# Connectors.net
KiCad netlist of a schematic drawn in Altium Designer
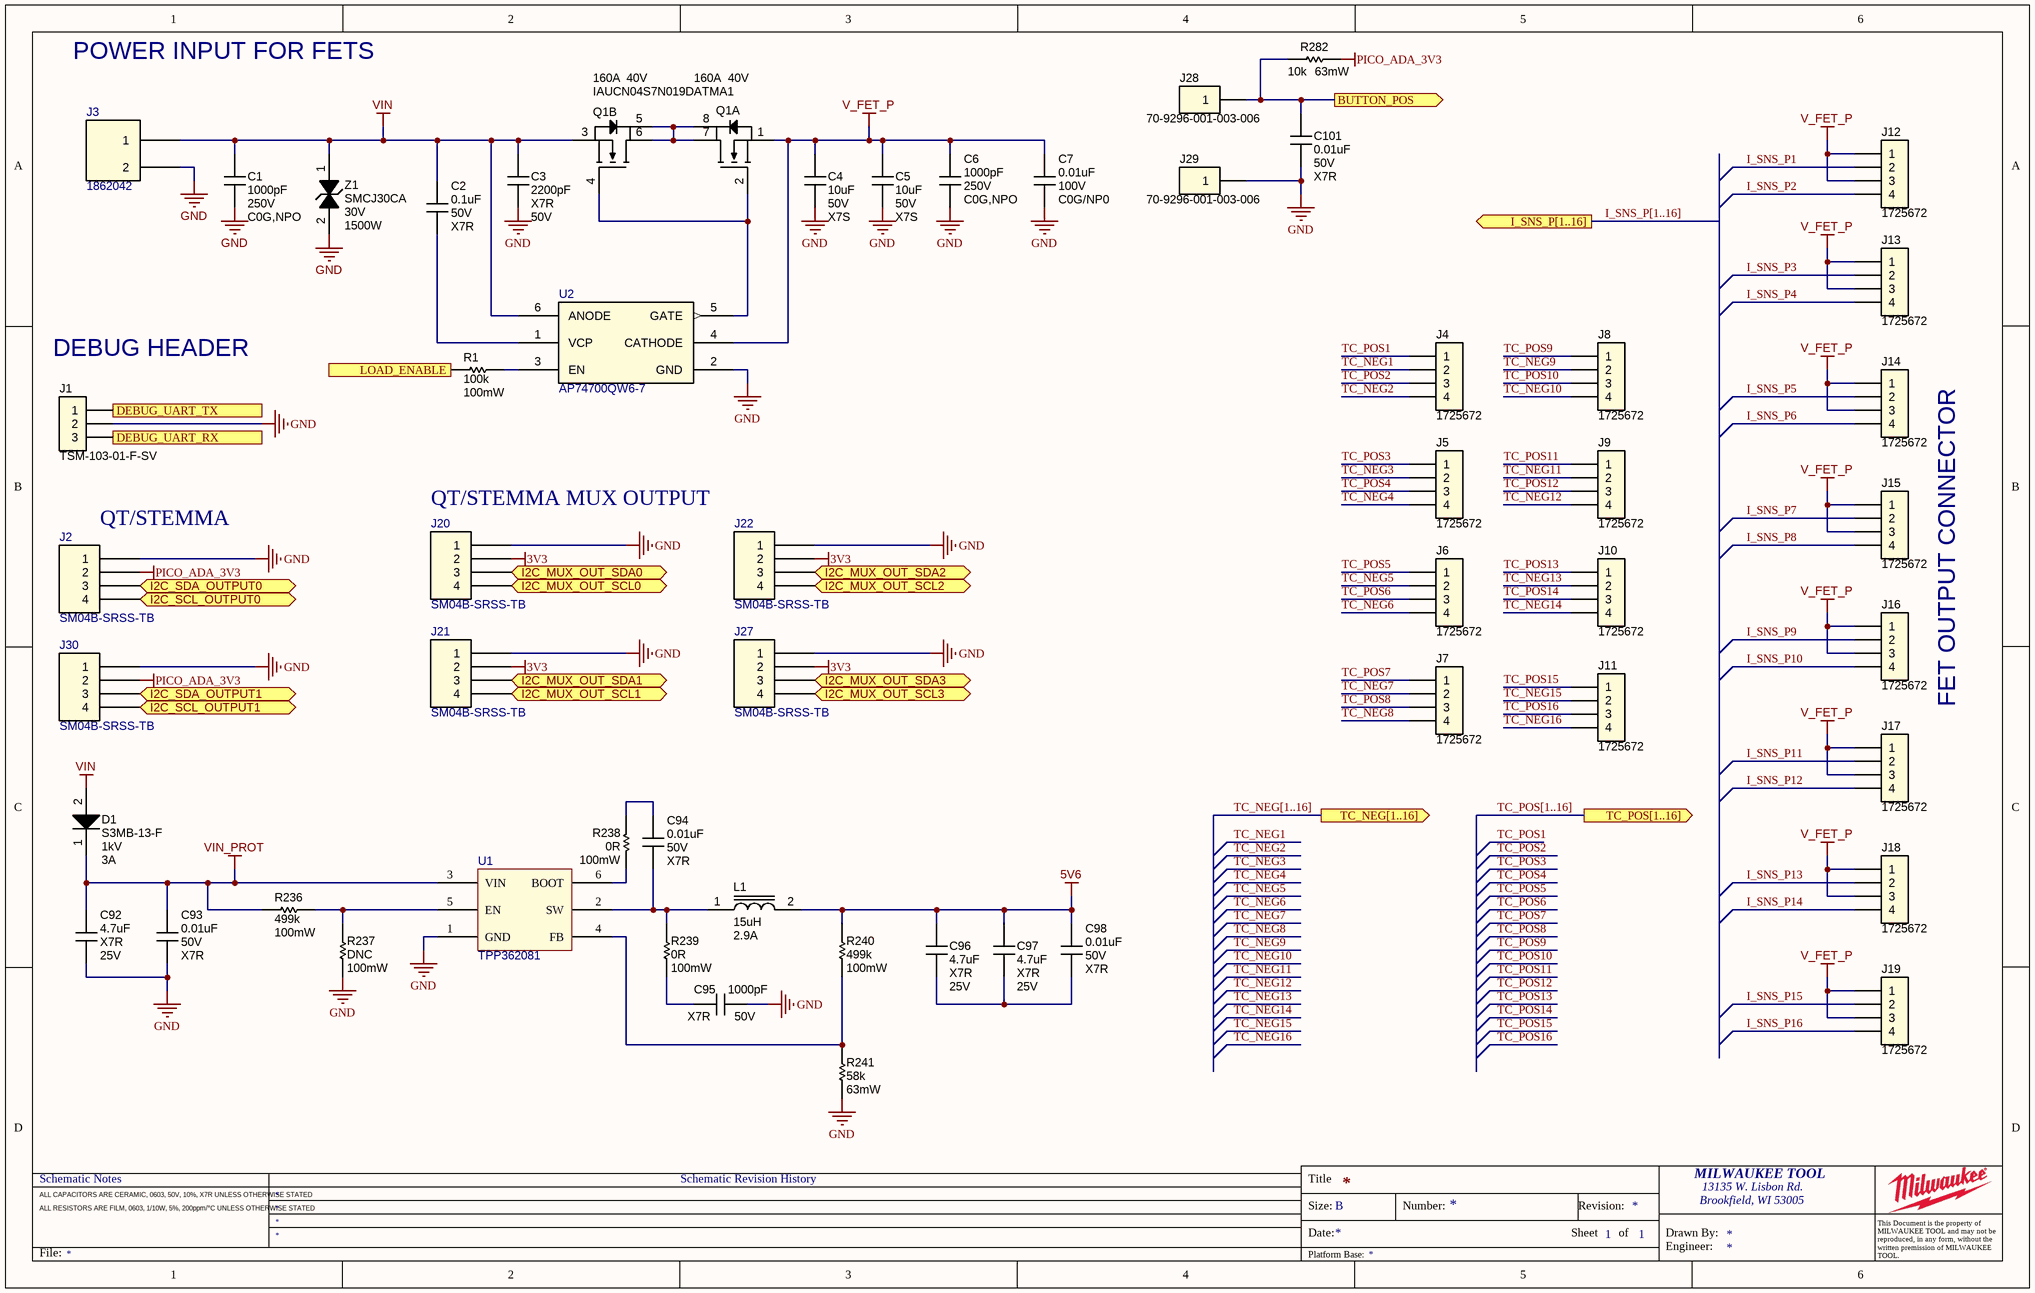
[diagram p0: Connectors.SchDoc]

(export (version "E")
  (design (tool "Eeschema 10.0.6"))
  (components
    (comp (ref "C1")
      (value "1000pF")
      (footprint "CAPC1608X09N")
      (description "CAP CER 1000PF 250V X7R 0603")
      (fields
        (field (name "TOLERANCE") "5%")
        (field (name "MFR") "KEMET")
        (field (name "VOLTAGE RATING") "250V")
        (field (name "TEMP COEFF") "C0G,NPO")
      )
      (libsource (lib "General_Library") (part "CMP-004-0013"))
    )
    (comp (ref "C2")
      (value "0.1uF")
      (footprint "CAPC1005X06N")
      (description "CAP CER SMD 0.1UF 50V X7R 0402")
      (fields
        (field (name "TOLERANCE") "10%")
        (field (name "MFR") "Murata Electronics")
        (field (name "VOLTAGE RATING") "50V")
        (field (name "TEMP COEFF") "X7R")
      )
      (libsource (lib "General_Library") (part "CMP-004-0076"))
    )
    (comp (ref "C3")
      (value "2200pF")
      (footprint "CAPC1608X09N")
      (description "CAP CER 2200PF 50V X7R 0603")
      (fields
        (field (name "TOLERANCE") "10%")
        (field (name "MFR") "KEMET")
        (field (name "TEMP COEFF") "X7R")
        (field (name "VOLTAGE RATING") "50V")
      )
      (libsource (lib "General_Library") (part "CMP-004-0009"))
    )
    (comp (ref "C4")
      (value "10uF")
      (footprint "CAPC3225X28N")
      (description "CAP, CER, 10µF, 50V, 10%, X7S, 1210")
      (fields
        (field (name "MFR") "TDK Corporation")
        (field (name "TOLERANCE") "10%")
        (field (name "VOLTAGE RATING") "50V")
        (field (name "TEMP COEFF") "X7S")
      )
      (libsource (lib "General_Library") (part "CMP-004-0001"))
    )
    (comp (ref "C5")
      (value "10uF")
      (footprint "CAPC3225X28N")
      (description "CAP, CER, 10µF, 50V, 10%, X7S, 1210")
      (fields
        (field (name "MFR") "TDK Corporation")
        (field (name "TOLERANCE") "10%")
        (field (name "VOLTAGE RATING") "50V")
        (field (name "TEMP COEFF") "X7S")
      )
      (libsource (lib "General_Library") (part "CMP-004-0001"))
    )
    (comp (ref "C6")
      (value "1000pF")
      (footprint "CAPC1608X09N")
      (description "CAP CER 1000PF 250V X7R 0603")
      (fields
        (field (name "TOLERANCE") "5%")
        (field (name "MFR") "KEMET")
        (field (name "VOLTAGE RATING") "250V")
        (field (name "TEMP COEFF") "C0G,NPO")
      )
      (libsource (lib "General_Library") (part "CMP-004-0013"))
    )
    (comp (ref "C7")
      (value "0.01uF")
      (footprint "CAPC1608X09N")
      (description "CAP CER 1000PF 100V C0G/NP0 0603")
      (fields
        (field (name "MFR") "Murata Electronics")
        (field (name "TOLERANCE") "10%")
        (field (name "VOLTAGE RATING") "100V")
        (field (name "TEMP COEFF") "C0G/NP0")
      )
      (libsource (lib "General_Library") (part "CMP-004-0027"))
    )
    (comp (ref "C92")
      (value "4.7uF")
      (footprint "CAPC2012X14N")
      (description "CAP CER 4.7UF 25V X7R 0805")
      (fields
        (field (name "MFR") "TDK Corporation")
        (field (name "TOLERANCE") "10%")
        (field (name "TEMP COEFF") "X7R")
        (field (name "VOLTAGE RATING") "25V")
      )
      (libsource (lib "General_Library") (part "CMP-004-0011"))
    )
    (comp (ref "C93")
      (value "0.01uF")
      (footprint "CAPC1608X09N")
      (description "CAP CER 10000PF (0.01uF) 50V X7R 0603")
      (fields
        (field (name "TOLERANCE") "10%")
        (field (name "MFR") "KYOCERA AVX")
        (field (name "VOLTAGE RATING") "50V")
        (field (name "TEMP COEFF") "X7R")
      )
      (libsource (lib "General_Library") (part "CMP-004-0069"))
    )
    (comp (ref "C94")
      (value "0.01uF")
      (footprint "CAPC1608X09N")
      (description "CAP CER 10000PF (0.01uF) 50V X7R 0603")
      (fields
        (field (name "TOLERANCE") "10%")
        (field (name "MFR") "KYOCERA AVX")
        (field (name "VOLTAGE RATING") "50V")
        (field (name "TEMP COEFF") "X7R")
      )
      (libsource (lib "General_Library") (part "CMP-004-0069"))
    )
    (comp (ref "C95")
      (value "1000pF")
      (footprint "CAPC1608X09N")
      (description "CAP CER 1000PF 50V X7R 0603")
      (fields
        (field (name "MFR") "Yageo")
        (field (name "TOLERANCE") "10%")
        (field (name "TEMP COEFF") "X7R")
        (field (name "VOLTAGE RATING") "50V")
      )
      (libsource (lib "General_Library") (part "CMP-004-0050"))
    )
    (comp (ref "C96")
      (value "4.7uF")
      (footprint "CAPC2012X14N")
      (description "CAP CER 4.7UF 25V X7R 0805")
      (fields
        (field (name "MFR") "TDK Corporation")
        (field (name "TOLERANCE") "10%")
        (field (name "TEMP COEFF") "X7R")
        (field (name "VOLTAGE RATING") "25V")
      )
      (libsource (lib "General_Library") (part "CMP-004-0011"))
    )
    (comp (ref "C97")
      (value "4.7uF")
      (footprint "CAPC2012X14N")
      (description "CAP CER 4.7UF 25V X7R 0805")
      (fields
        (field (name "MFR") "TDK Corporation")
        (field (name "TOLERANCE") "10%")
        (field (name "TEMP COEFF") "X7R")
        (field (name "VOLTAGE RATING") "25V")
      )
      (libsource (lib "General_Library") (part "CMP-004-0011"))
    )
    (comp (ref "C98")
      (value "0.01uF")
      (footprint "CAPC1608X09N")
      (description "CAP CER 10000PF (0.01uF) 50V X7R 0603")
      (fields
        (field (name "TOLERANCE") "10%")
        (field (name "MFR") "KYOCERA AVX")
        (field (name "VOLTAGE RATING") "50V")
        (field (name "TEMP COEFF") "X7R")
      )
      (libsource (lib "General_Library") (part "CMP-004-0069"))
    )
    (comp (ref "C101")
      (value "0.01uF")
      (footprint "CAPC1608X09N")
      (description "CAP CER 10000PF (0.01uF) 50V X7R 0603")
      (fields
        (field (name "TOLERANCE") "10%")
        (field (name "MFR") "KYOCERA AVX")
        (field (name "VOLTAGE RATING") "50V")
        (field (name "TEMP COEFF") "X7R")
      )
      (libsource (lib "General_Library") (part "CMP-004-0069"))
    )
    (comp (ref "D1")
      (value "S3MB-13-F")
      (footprint "DIOM4336X25N")
      (description "DIODE GEN PURP 1KV 3A SMB")
      (fields
        (field (name "MFR") "Diodes Incorporated")
        (field (name "VOLTAGE RATING") "1kV")
        (field (name "CURRENT RATING") "3A")
      )
      (libsource (lib "General_Library") (part "CMP-010-0001"))
    )
    (comp (ref "J1")
      (value "TSM-103-01-F-SV")
      (footprint "CONN_SAMTEC_TSM-103-01-F-SV")
      (description "CONN HEADER SMD 3POS 2.54MM")
      (fields (field (name "MFR") "Samtec"))
      (libsource (lib "General_Library") (part "CMP-007-0021"))
    )
    (comp (ref "J2")
      (value "SM04B-SRSS-TB")
      (footprint "Footprints:CONN_JST_SM04B-SRSS-TB_JST")
      (description "CONN HEADER SMD R/A SH 4POS 1MM")
      (fields (field (name "MFR") "JST"))
      (libsource (lib "Symbols") (part "CMP-007-0084"))
    )
    (comp (ref "J3")
      (value "1862042")
      (footprint "Footprints:CONN_PHOENIX_1862042")
      (description "TERM BLOCK 2POS 45DEG 3.5MM PCB")
      (fields (field (name "MFR") "Phoenix"))
      (libsource (lib "Symbols") (part "CMP-007-0077"))
    )
    (comp (ref "J4")
      (value "1725672")
      (footprint "CONN_PHOENIX_1725672")
      (description "TERM BLK 4P SIDE ENT 2.54MM PCB")
      (fields (field (name "MFR") "Phoenix Contact"))
      (libsource (lib "General_Library") (part "CMP-007-0053"))
    )
    (comp (ref "J5")
      (value "1725672")
      (footprint "CONN_PHOENIX_1725672")
      (description "TERM BLK 4P SIDE ENT 2.54MM PCB")
      (fields (field (name "MFR") "Phoenix Contact"))
      (libsource (lib "General_Library") (part "CMP-007-0053"))
    )
    (comp (ref "J6")
      (value "1725672")
      (footprint "CONN_PHOENIX_1725672")
      (description "TERM BLK 4P SIDE ENT 2.54MM PCB")
      (fields (field (name "MFR") "Phoenix Contact"))
      (libsource (lib "General_Library") (part "CMP-007-0053"))
    )
    (comp (ref "J7")
      (value "1725672")
      (footprint "CONN_PHOENIX_1725672")
      (description "TERM BLK 4P SIDE ENT 2.54MM PCB")
      (fields (field (name "MFR") "Phoenix Contact"))
      (libsource (lib "General_Library") (part "CMP-007-0053"))
    )
    (comp (ref "J8")
      (value "1725672")
      (footprint "CONN_PHOENIX_1725672")
      (description "TERM BLK 4P SIDE ENT 2.54MM PCB")
      (fields (field (name "MFR") "Phoenix Contact"))
      (libsource (lib "General_Library") (part "CMP-007-0053"))
    )
    (comp (ref "J9")
      (value "1725672")
      (footprint "CONN_PHOENIX_1725672")
      (description "TERM BLK 4P SIDE ENT 2.54MM PCB")
      (fields (field (name "MFR") "Phoenix Contact"))
      (libsource (lib "General_Library") (part "CMP-007-0053"))
    )
    (comp (ref "J10")
      (value "1725672")
      (footprint "CONN_PHOENIX_1725672")
      (description "TERM BLK 4P SIDE ENT 2.54MM PCB")
      (fields (field (name "MFR") "Phoenix Contact"))
      (libsource (lib "General_Library") (part "CMP-007-0053"))
    )
    (comp (ref "J11")
      (value "1725672")
      (footprint "CONN_PHOENIX_1725672")
      (description "TERM BLK 4P SIDE ENT 2.54MM PCB")
      (fields (field (name "MFR") "Phoenix Contact"))
      (libsource (lib "General_Library") (part "CMP-007-0053"))
    )
    (comp (ref "J12")
      (value "1725672")
      (footprint "CONN_PHOENIX_1725672")
      (description "TERM BLK 4P SIDE ENT 2.54MM PCB")
      (fields (field (name "MFR") "Phoenix Contact"))
      (libsource (lib "General_Library") (part "CMP-007-0053"))
    )
    (comp (ref "J13")
      (value "1725672")
      (footprint "CONN_PHOENIX_1725672")
      (description "TERM BLK 4P SIDE ENT 2.54MM PCB")
      (fields (field (name "MFR") "Phoenix Contact"))
      (libsource (lib "General_Library") (part "CMP-007-0053"))
    )
    (comp (ref "J14")
      (value "1725672")
      (footprint "CONN_PHOENIX_1725672")
      (description "TERM BLK 4P SIDE ENT 2.54MM PCB")
      (fields (field (name "MFR") "Phoenix Contact"))
      (libsource (lib "General_Library") (part "CMP-007-0053"))
    )
    (comp (ref "J15")
      (value "1725672")
      (footprint "CONN_PHOENIX_1725672")
      (description "TERM BLK 4P SIDE ENT 2.54MM PCB")
      (fields (field (name "MFR") "Phoenix Contact"))
      (libsource (lib "General_Library") (part "CMP-007-0053"))
    )
    (comp (ref "J16")
      (value "1725672")
      (footprint "CONN_PHOENIX_1725672")
      (description "TERM BLK 4P SIDE ENT 2.54MM PCB")
      (fields (field (name "MFR") "Phoenix Contact"))
      (libsource (lib "General_Library") (part "CMP-007-0053"))
    )
    (comp (ref "J17")
      (value "1725672")
      (footprint "CONN_PHOENIX_1725672")
      (description "TERM BLK 4P SIDE ENT 2.54MM PCB")
      (fields (field (name "MFR") "Phoenix Contact"))
      (libsource (lib "General_Library") (part "CMP-007-0053"))
    )
    (comp (ref "J18")
      (value "1725672")
      (footprint "CONN_PHOENIX_1725672")
      (description "TERM BLK 4P SIDE ENT 2.54MM PCB")
      (fields (field (name "MFR") "Phoenix Contact"))
      (libsource (lib "General_Library") (part "CMP-007-0053"))
    )
    (comp (ref "J19")
      (value "1725672")
      (footprint "CONN_PHOENIX_1725672")
      (description "TERM BLK 4P SIDE ENT 2.54MM PCB")
      (fields (field (name "MFR") "Phoenix Contact"))
      (libsource (lib "General_Library") (part "CMP-007-0053"))
    )
    (comp (ref "J20")
      (value "SM04B-SRSS-TB")
      (footprint "Footprints:CONN_JST_SM04B-SRSS-TB_JST")
      (description "CONN HEADER SMD R/A SH 4POS 1MM")
      (fields (field (name "MFR") "JST"))
      (libsource (lib "Symbols") (part "CMP-007-0084"))
    )
    (comp (ref "J21")
      (value "SM04B-SRSS-TB")
      (footprint "Footprints:CONN_JST_SM04B-SRSS-TB_JST")
      (description "CONN HEADER SMD R/A SH 4POS 1MM")
      (fields (field (name "MFR") "JST"))
      (libsource (lib "Symbols") (part "CMP-007-0084"))
    )
    (comp (ref "J22")
      (value "SM04B-SRSS-TB")
      (footprint "Footprints:CONN_JST_SM04B-SRSS-TB_JST")
      (description "CONN HEADER SMD R/A SH 4POS 1MM")
      (fields (field (name "MFR") "JST"))
      (libsource (lib "Symbols") (part "CMP-007-0084"))
    )
    (comp (ref "J27")
      (value "SM04B-SRSS-TB")
      (footprint "Footprints:CONN_JST_SM04B-SRSS-TB_JST")
      (description "CONN HEADER SMD R/A SH 4POS 1MM")
      (fields (field (name "MFR") "JST"))
      (libsource (lib "Symbols") (part "CMP-007-0084"))
    )
    (comp (ref "J28")
      (value "70-9296-001-003-006")
      (footprint "AVX_709296001003006")
      (description "CONN SSL POKE-IN CONT 18-26AWG")
      (fields (field (name "MFR") "AVX"))
      (libsource (lib "Symbols") (part "CMP-007-0008"))
    )
    (comp (ref "J29")
      (value "70-9296-001-003-006")
      (footprint "AVX_709296001003006")
      (description "CONN SSL POKE-IN CONT 18-26AWG")
      (fields (field (name "MFR") "AVX"))
      (libsource (lib "Symbols") (part "CMP-007-0008"))
    )
    (comp (ref "J30")
      (value "SM04B-SRSS-TB")
      (footprint "Footprints:CONN_JST_SM04B-SRSS-TB_JST")
      (description "CONN HEADER SMD R/A SH 4POS 1MM")
      (fields (field (name "MFR") "JST"))
      (libsource (lib "Symbols") (part "CMP-007-0084"))
    )
    (comp (ref "L1")
      (value "15uH")
      (footprint "INDM6565X30N")
      (description "FIXED IND 15UH 2.9A 127 MOHM SMD")
      (fields
        (field (name "MFR") "Vishay Dale")
        (field (name "TOLERANCE") "20%")
        (field (name "CURRENT RATING") "2.9A")
      )
      (libsource (lib "General_Library") (part "CMP-018-0005"))
    )
    (comp (ref "Q1")
      (value "IAUCN04S7N019DATMA1")
      (footprint "INF-PG-TDSON-8-61-V")
      (description "TRANS DUAL MOSFET N-CH 40V 160A PG-TDSON-8-60")
      (fields (field (name "MFR") "Infineon") (field (name "CURRENT") "160A") (field (name "VOLTAGE") "40V"))
      (libsource (lib "General_Library") (part "CMP-029-0048"))
    )
    (comp (ref "R1")
      (value "100k")
      (footprint "RESC1608X06N")
      (description "RES SMD 100K OHM 1% 1/10W 0603")
      (fields
        (field (name "MFR") "Panasonic Electronic Components")
        (field (name "TOLERANCE") "1%")
        (field (name "WATTAGE") "100mW")
      )
      (libsource (lib "General_Library") (part "CMP-025-0099"))
    )
    (comp (ref "R236")
      (value "499k")
      (footprint "RESC1608X06N")
      (description "RES SMD 499k OHM 1% 1/10W 0603")
      (fields
        (field (name "MFR") "Panasonic Electronic Components")
        (field (name "TOLERANCE") "1%")
        (field (name "WATTAGE") "100mW")
      )
      (libsource (lib "General_Library") (part "CMP-025-0006"))
    )
    (comp (ref "R237")
      (value "DNC")
      (footprint "RESC1608X06N")
      (description "RES SMD 0 OHM JUMPER 1/10W 0603")
      (fields
        (field (name "VOLTAGE") "75V")
        (field (name "TOLERANCE") "Jumper")
        (field (name "WATTAGE") "100mW")
      )
      (libsource (lib "General_Library") (part "CMP-025-0103"))
    )
    (comp (ref "R238")
      (value "0R")
      (footprint "RESC1608X06N")
      (description "RES SMD 0 OHM JUMPER 1/10W 0603")
      (fields
        (field (name "VOLTAGE") "75V")
        (field (name "TOLERANCE") "Jumper")
        (field (name "WATTAGE") "100mW")
      )
      (libsource (lib "General_Library") (part "CMP-025-0103"))
    )
    (comp (ref "R239")
      (value "0R")
      (footprint "RESC1608X06N")
      (description "RES SMD 0 OHM JUMPER 1/10W 0603")
      (fields
        (field (name "VOLTAGE") "75V")
        (field (name "TOLERANCE") "Jumper")
        (field (name "WATTAGE") "100mW")
      )
      (libsource (lib "General_Library") (part "CMP-025-0103"))
    )
    (comp (ref "R240")
      (value "499k")
      (footprint "RESC1608X06N")
      (description "RES SMD 499k OHM 1% 1/10W 0603")
      (fields
        (field (name "MFR") "Panasonic Electronic Components")
        (field (name "TOLERANCE") "1%")
        (field (name "WATTAGE") "100mW")
      )
      (libsource (lib "General_Library") (part "CMP-025-0006"))
    )
    (comp (ref "R241")
      (value "58k")
      (footprint "RESC1005X04N")
      (description "RES SMD 58K OHM 1% 1/16W 0402")
      (fields (field (name "TOLERANCE") "1%") (field (name "MFR") "Yageo") (field (name "WATTAGE") "63mW"))
      (libsource (lib "General_Library") (part "CMP-025-0175"))
    )
    (comp (ref "R282")
      (value "10k")
      (footprint "RESC1005X04N")
      (description "RES SMD 10K OHM 0.5% 1/16W 0402")
      (fields
        (field (name "MFR") "Panasonic Electronic Components")
        (field (name "TOLERANCE") "0.5%")
        (field (name "WATTAGE") "63mW")
      )
      (libsource (lib "General_Library") (part "CMP-025-0026"))
    )
    (comp (ref "U1")
      (value "TPP362081")
      (footprint "SOT95P280X95-6N")
      (description "IC OPAMP VFB 1 CIRCUIT 8HVSSOP")
      (fields (field (name "MFR") "3PEAK"))
      (libsource (lib "General_Library") (part "CMP-017-0119"))
    )
    (comp (ref "U2")
      (value "AP74700QW6-7")
      (footprint "Footprints:SOT95P285X140-6N")
      (description "IC LOAD SWITCH SOT26 T&R 3K")
      (fields (field (name "MFR") "Diodes Inc"))
      (libsource (lib "Symbols") (part "CMP-017-0114"))
    )
    (comp (ref "Z1")
      (value "SMCJ30CA")
      (footprint "DIOM6959X26N")
      (description "TVS DIODE 30VWM 48.4VC DO214AB")
      (fields
        (field (name "MFR") "Micro Commercial Co")
        (field (name "VOLTAGE") "30V")
        (field (name "WATTAGE") "1500W")
      )
      (libsource (lib "General_Library") (part "CMP-014-0007"))
    )
  )
  (nets
    (net (code "1") (name "/BUTTON_POS") (class "Default")
      (node (ref "C101") (pin "2") (pinfunction "2_2") (pintype "passive"))
      (node (ref "J28") (pin "1") (pinfunction "1_1") (pintype "passive"))
      (node (ref "R282") (pin "1") (pinfunction "1_1") (pintype "passive"))
    )
    (net (code "2") (name "/DEBUG_UART_RX") (class "Default")
      (node (ref "J1") (pin "3") (pinfunction "3_3") (pintype "passive"))
    )
    (net (code "3") (name "/DEBUG_UART_TX") (class "Default")
      (node (ref "J1") (pin "1") (pinfunction "1_1") (pintype "passive"))
    )
    (net (code "4") (name "/I2C_MUX_OUT_SCL0") (class "Default")
      (node (ref "J20") (pin "4") (pinfunction "4_4") (pintype "passive"))
    )
    (net (code "5") (name "/I2C_MUX_OUT_SCL1") (class "Default")
      (node (ref "J21") (pin "4") (pinfunction "4_4") (pintype "passive"))
    )
    (net (code "6") (name "/I2C_MUX_OUT_SCL2") (class "Default")
      (node (ref "J22") (pin "4") (pinfunction "4_4") (pintype "passive"))
    )
    (net (code "7") (name "/I2C_MUX_OUT_SCL3") (class "Default")
      (node (ref "J27") (pin "4") (pinfunction "4_4") (pintype "passive"))
    )
    (net (code "8") (name "/I2C_MUX_OUT_SDA0") (class "Default")
      (node (ref "J20") (pin "3") (pinfunction "3_3") (pintype "passive"))
    )
    (net (code "9") (name "/I2C_MUX_OUT_SDA1") (class "Default")
      (node (ref "J21") (pin "3") (pinfunction "3_3") (pintype "passive"))
    )
    (net (code "10") (name "/I2C_MUX_OUT_SDA2") (class "Default")
      (node (ref "J22") (pin "3") (pinfunction "3_3") (pintype "passive"))
    )
    (net (code "11") (name "/I2C_MUX_OUT_SDA3") (class "Default")
      (node (ref "J27") (pin "3") (pinfunction "3_3") (pintype "passive"))
    )
    (net (code "12") (name "/I2C_SCL_OUTPUT0") (class "Default")
      (node (ref "J2") (pin "4") (pinfunction "4_4") (pintype "passive"))
    )
    (net (code "13") (name "/I2C_SCL_OUTPUT1") (class "Default")
      (node (ref "J30") (pin "4") (pinfunction "4_4") (pintype "passive"))
    )
    (net (code "14") (name "/I2C_SDA_OUTPUT0") (class "Default")
      (node (ref "J2") (pin "3") (pinfunction "3_3") (pintype "passive"))
    )
    (net (code "15") (name "/I2C_SDA_OUTPUT1") (class "Default")
      (node (ref "J30") (pin "3") (pinfunction "3_3") (pintype "passive"))
    )
    (net (code "16") (name "/I_SNS_P1") (class "Default")
      (node (ref "J12") (pin "2") (pinfunction "2_2") (pintype "passive"))
    )
    (net (code "17") (name "/I_SNS_P2") (class "Default")
      (node (ref "J12") (pin "4") (pinfunction "4_4") (pintype "passive"))
    )
    (net (code "18") (name "/I_SNS_P3") (class "Default")
      (node (ref "J13") (pin "2") (pinfunction "2_2") (pintype "passive"))
    )
    (net (code "19") (name "/I_SNS_P4") (class "Default")
      (node (ref "J13") (pin "4") (pinfunction "4_4") (pintype "passive"))
    )
    (net (code "20") (name "/I_SNS_P5") (class "Default")
      (node (ref "J14") (pin "2") (pinfunction "2_2") (pintype "passive"))
    )
    (net (code "21") (name "/I_SNS_P6") (class "Default")
      (node (ref "J14") (pin "4") (pinfunction "4_4") (pintype "passive"))
    )
    (net (code "22") (name "/I_SNS_P7") (class "Default")
      (node (ref "J15") (pin "2") (pinfunction "2_2") (pintype "passive"))
    )
    (net (code "23") (name "/I_SNS_P8") (class "Default")
      (node (ref "J15") (pin "4") (pinfunction "4_4") (pintype "passive"))
    )
    (net (code "24") (name "/I_SNS_P9") (class "Default")
      (node (ref "J16") (pin "2") (pinfunction "2_2") (pintype "passive"))
    )
    (net (code "25") (name "/I_SNS_P10") (class "Default")
      (node (ref "J16") (pin "4") (pinfunction "4_4") (pintype "passive"))
    )
    (net (code "26") (name "/I_SNS_P11") (class "Default")
      (node (ref "J17") (pin "2") (pinfunction "2_2") (pintype "passive"))
    )
    (net (code "27") (name "/I_SNS_P12") (class "Default")
      (node (ref "J17") (pin "4") (pinfunction "4_4") (pintype "passive"))
    )
    (net (code "28") (name "/I_SNS_P13") (class "Default")
      (node (ref "J18") (pin "2") (pinfunction "2_2") (pintype "passive"))
    )
    (net (code "29") (name "/I_SNS_P14") (class "Default")
      (node (ref "J18") (pin "4") (pinfunction "4_4") (pintype "passive"))
    )
    (net (code "30") (name "/I_SNS_P15") (class "Default")
      (node (ref "J19") (pin "2") (pinfunction "2_2") (pintype "passive"))
    )
    (net (code "31") (name "/I_SNS_P16") (class "Default")
      (node (ref "J19") (pin "4") (pinfunction "4_4") (pintype "passive"))
    )
    (net (code "33") (name "/LOAD_ENABLE") (class "Default")
      (node (ref "R1") (pin "2") (pinfunction "2_2") (pintype "passive"))
    )
    (net (code "34") (name "/TC_NEG1") (class "Default")
      (node (ref "J4") (pin "2") (pinfunction "2_2") (pintype "passive"))
    )
    (net (code "35") (name "/TC_NEG2") (class "Default")
      (node (ref "J4") (pin "4") (pinfunction "4_4") (pintype "passive"))
    )
    (net (code "36") (name "/TC_NEG3") (class "Default")
      (node (ref "J5") (pin "2") (pinfunction "2_2") (pintype "passive"))
    )
    (net (code "37") (name "/TC_NEG4") (class "Default")
      (node (ref "J5") (pin "4") (pinfunction "4_4") (pintype "passive"))
    )
    (net (code "38") (name "/TC_NEG5") (class "Default")
      (node (ref "J6") (pin "2") (pinfunction "2_2") (pintype "passive"))
    )
    (net (code "39") (name "/TC_NEG6") (class "Default")
      (node (ref "J6") (pin "4") (pinfunction "4_4") (pintype "passive"))
    )
    (net (code "40") (name "/TC_NEG7") (class "Default")
      (node (ref "J7") (pin "2") (pinfunction "2_2") (pintype "passive"))
    )
    (net (code "41") (name "/TC_NEG8") (class "Default")
      (node (ref "J7") (pin "4") (pinfunction "4_4") (pintype "passive"))
    )
    (net (code "42") (name "/TC_NEG9") (class "Default")
      (node (ref "J8") (pin "2") (pinfunction "2_2") (pintype "passive"))
    )
    (net (code "43") (name "/TC_NEG10") (class "Default")
      (node (ref "J8") (pin "4") (pinfunction "4_4") (pintype "passive"))
    )
    (net (code "44") (name "/TC_NEG11") (class "Default")
      (node (ref "J9") (pin "2") (pinfunction "2_2") (pintype "passive"))
    )
    (net (code "45") (name "/TC_NEG12") (class "Default")
      (node (ref "J9") (pin "4") (pinfunction "4_4") (pintype "passive"))
    )
    (net (code "46") (name "/TC_NEG13") (class "Default")
      (node (ref "J10") (pin "2") (pinfunction "2_2") (pintype "passive"))
    )
    (net (code "47") (name "/TC_NEG14") (class "Default")
      (node (ref "J10") (pin "4") (pinfunction "4_4") (pintype "passive"))
    )
    (net (code "48") (name "/TC_NEG15") (class "Default")
      (node (ref "J11") (pin "2") (pinfunction "2_2") (pintype "passive"))
    )
    (net (code "49") (name "/TC_NEG16") (class "Default")
      (node (ref "J11") (pin "4") (pinfunction "4_4") (pintype "passive"))
    )
    (net (code "51") (name "/TC_POS1") (class "Default")
      (node (ref "J4") (pin "1") (pinfunction "1_1") (pintype "passive"))
    )
    (net (code "52") (name "/TC_POS2") (class "Default")
      (node (ref "J4") (pin "3") (pinfunction "3_3") (pintype "passive"))
    )
    (net (code "53") (name "/TC_POS3") (class "Default")
      (node (ref "J5") (pin "1") (pinfunction "1_1") (pintype "passive"))
    )
    (net (code "54") (name "/TC_POS4") (class "Default")
      (node (ref "J5") (pin "3") (pinfunction "3_3") (pintype "passive"))
    )
    (net (code "55") (name "/TC_POS5") (class "Default")
      (node (ref "J6") (pin "1") (pinfunction "1_1") (pintype "passive"))
    )
    (net (code "56") (name "/TC_POS6") (class "Default")
      (node (ref "J6") (pin "3") (pinfunction "3_3") (pintype "passive"))
    )
    (net (code "57") (name "/TC_POS7") (class "Default")
      (node (ref "J7") (pin "1") (pinfunction "1_1") (pintype "passive"))
    )
    (net (code "58") (name "/TC_POS8") (class "Default")
      (node (ref "J7") (pin "3") (pinfunction "3_3") (pintype "passive"))
    )
    (net (code "59") (name "/TC_POS9") (class "Default")
      (node (ref "J8") (pin "1") (pinfunction "1_1") (pintype "passive"))
    )
    (net (code "60") (name "/TC_POS10") (class "Default")
      (node (ref "J8") (pin "3") (pinfunction "3_3") (pintype "passive"))
    )
    (net (code "61") (name "/TC_POS11") (class "Default")
      (node (ref "J9") (pin "1") (pinfunction "1_1") (pintype "passive"))
    )
    (net (code "62") (name "/TC_POS12") (class "Default")
      (node (ref "J9") (pin "3") (pinfunction "3_3") (pintype "passive"))
    )
    (net (code "63") (name "/TC_POS13") (class "Default")
      (node (ref "J10") (pin "1") (pinfunction "1_1") (pintype "passive"))
    )
    (net (code "64") (name "/TC_POS14") (class "Default")
      (node (ref "J10") (pin "3") (pinfunction "3_3") (pintype "passive"))
    )
    (net (code "65") (name "/TC_POS15") (class "Default")
      (node (ref "J11") (pin "1") (pinfunction "1_1") (pintype "passive"))
    )
    (net (code "66") (name "/TC_POS16") (class "Default")
      (node (ref "J11") (pin "3") (pinfunction "3_3") (pintype "passive"))
    )
    (net (code "68") (name "3V3") (class "Default")
      (node (ref "J20") (pin "2") (pinfunction "2_2") (pintype "passive"))
      (node (ref "J21") (pin "2") (pinfunction "2_2") (pintype "passive"))
      (node (ref "J22") (pin "2") (pinfunction "2_2") (pintype "passive"))
      (node (ref "J27") (pin "2") (pinfunction "2_2") (pintype "passive"))
    )
    (net (code "69") (name "5V6") (class "Default")
      (node (ref "C96") (pin "1") (pinfunction "1_1") (pintype "passive"))
      (node (ref "C97") (pin "1") (pinfunction "1_1") (pintype "passive"))
      (node (ref "C98") (pin "2") (pinfunction "2_2") (pintype "passive"))
      (node (ref "L1") (pin "2") (pinfunction "2_2") (pintype "passive"))
      (node (ref "R240") (pin "2") (pinfunction "2_2") (pintype "passive"))
    )
    (net (code "70") (name "GND") (class "Default")
      (node (ref "C1") (pin "2") (pinfunction "2_2") (pintype "passive"))
      (node (ref "C101") (pin "1") (pinfunction "1_1") (pintype "passive"))
      (node (ref "C3") (pin "2") (pinfunction "2_2") (pintype "passive"))
      (node (ref "C4") (pin "2") (pinfunction "2_2") (pintype "passive"))
      (node (ref "C5") (pin "2") (pinfunction "2_2") (pintype "passive"))
      (node (ref "C6") (pin "2") (pinfunction "2_2") (pintype "passive"))
      (node (ref "C7") (pin "2") (pinfunction "2_2") (pintype "passive"))
      (node (ref "C92") (pin "2") (pinfunction "2_2") (pintype "passive"))
      (node (ref "C93") (pin "1") (pinfunction "1_1") (pintype "passive"))
      (node (ref "C95") (pin "2") (pinfunction "2_2") (pintype "passive"))
      (node (ref "J1") (pin "2") (pinfunction "2_2") (pintype "passive"))
      (node (ref "J2") (pin "1") (pinfunction "1_1") (pintype "passive"))
      (node (ref "J20") (pin "1") (pinfunction "1_1") (pintype "passive"))
      (node (ref "J21") (pin "1") (pinfunction "1_1") (pintype "passive"))
      (node (ref "J22") (pin "1") (pinfunction "1_1") (pintype "passive"))
      (node (ref "J27") (pin "1") (pinfunction "1_1") (pintype "passive"))
      (node (ref "J29") (pin "1") (pinfunction "1_1") (pintype "passive"))
      (node (ref "J3") (pin "2") (pinfunction "2_2") (pintype "passive"))
      (node (ref "J30") (pin "1") (pinfunction "1_1") (pintype "passive"))
      (node (ref "R237") (pin "2") (pinfunction "2_2") (pintype "passive"))
      (node (ref "R241") (pin "1") (pinfunction "1_1") (pintype "passive"))
      (node (ref "U1") (pin "1") (pinfunction "GND_1") (pintype "power_in"))
      (node (ref "U2") (pin "2") (pinfunction "GND_2") (pintype "passive"))
      (node (ref "Z1") (pin "2") (pinfunction "A_2") (pintype "passive"))
    )
    (net (code "71") (name "Net-(C94-Pad2)") (class "Default")
      (node (ref "C94") (pin "2") (pinfunction "2_2") (pintype "passive"))
      (node (ref "R238") (pin "1") (pinfunction "1_1") (pintype "passive"))
    )
    (net (code "72") (name "Net-(C95-Pad1)") (class "Default")
      (node (ref "C95") (pin "1") (pinfunction "1_1") (pintype "passive"))
      (node (ref "R239") (pin "1") (pinfunction "1_1") (pintype "passive"))
    )
    (net (code "73") (name "Net-(C96-Pad2)") (class "Default")
      (node (ref "C96") (pin "2") (pinfunction "2_2") (pintype "passive"))
      (node (ref "C97") (pin "2") (pinfunction "2_2") (pintype "passive"))
      (node (ref "C98") (pin "1") (pinfunction "1_1") (pintype "passive"))
    )
    (net (code "74") (name "Net-(Q1A-D-Pad7)") (class "Default")
      (node (ref "Q1") (pin "5") (pinfunction "D_5") (pintype "passive"))
      (node (ref "Q1") (pin "6") (pinfunction "D_6") (pintype "passive"))
      (node (ref "Q1") (pin "7") (pinfunction "D_7") (pintype "passive"))
      (node (ref "Q1") (pin "8") (pinfunction "D_8") (pintype "passive"))
    )
    (net (code "75") (name "Net-(Q1A-G)") (class "Default")
      (node (ref "Q1") (pin "2") (pinfunction "G_2") (pintype "passive"))
      (node (ref "Q1") (pin "4") (pinfunction "G_4") (pintype "passive"))
      (node (ref "U2") (pin "5") (pinfunction "GATE_5") (pintype "output"))
    )
    (net (code "76") (name "Net-(U1-BOOT)") (class "Default")
      (node (ref "R238") (pin "2") (pinfunction "2_2") (pintype "passive"))
      (node (ref "U1") (pin "6") (pinfunction "BOOT_6") (pintype "passive"))
    )
    (net (code "77") (name "Net-(U1-EN)") (class "Default")
      (node (ref "R236") (pin "2") (pinfunction "2_2") (pintype "passive"))
      (node (ref "R237") (pin "1") (pinfunction "1_1") (pintype "passive"))
      (node (ref "U1") (pin "5") (pinfunction "EN_5") (pintype "passive"))
    )
    (net (code "78") (name "Net-(U1-FB)") (class "Default")
      (node (ref "R240") (pin "1") (pinfunction "1_1") (pintype "passive"))
      (node (ref "R241") (pin "2") (pinfunction "2_2") (pintype "passive"))
      (node (ref "U1") (pin "4") (pinfunction "FB_4") (pintype "passive"))
    )
    (net (code "79") (name "Net-(U1-SW)") (class "Default")
      (node (ref "C94") (pin "1") (pinfunction "1_1") (pintype "passive"))
      (node (ref "L1") (pin "1") (pinfunction "1_1") (pintype "passive"))
      (node (ref "R239") (pin "2") (pinfunction "2_2") (pintype "passive"))
      (node (ref "U1") (pin "2") (pinfunction "SW_2") (pintype "passive"))
    )
    (net (code "80") (name "Net-(U2-EN)") (class "Default")
      (node (ref "R1") (pin "1") (pinfunction "1_1") (pintype "passive"))
      (node (ref "U2") (pin "3") (pinfunction "EN_3") (pintype "power_in"))
    )
    (net (code "81") (name "Net-(U2-VCP)") (class "Default")
      (node (ref "C2") (pin "2") (pinfunction "2_2") (pintype "passive"))
      (node (ref "U2") (pin "1") (pinfunction "VCP_1") (pintype "power_in"))
    )
    (net (code "82") (name "PICO_ADA_3V3") (class "Default")
      (node (ref "J2") (pin "2") (pinfunction "2_2") (pintype "passive"))
      (node (ref "J30") (pin "2") (pinfunction "2_2") (pintype "passive"))
      (node (ref "R282") (pin "2") (pinfunction "2_2") (pintype "passive"))
    )
    (net (code "83") (name "VIN") (class "Default")
      (node (ref "C1") (pin "1") (pinfunction "1_1") (pintype "passive"))
      (node (ref "C2") (pin "1") (pinfunction "1_1") (pintype "passive"))
      (node (ref "C3") (pin "1") (pinfunction "1_1") (pintype "passive"))
      (node (ref "D1") (pin "2") (pinfunction "Anode_2") (pintype "passive"))
      (node (ref "J3") (pin "1") (pinfunction "1_1") (pintype "passive"))
      (node (ref "Q1") (pin "3") (pinfunction "S_3") (pintype "passive"))
      (node (ref "U2") (pin "6") (pinfunction "ANODE_6") (pintype "passive"))
      (node (ref "Z1") (pin "1") (pinfunction "K_1") (pintype "passive"))
    )
    (net (code "84") (name "VIN_PROT") (class "Default")
      (node (ref "C92") (pin "1") (pinfunction "1_1") (pintype "passive"))
      (node (ref "C93") (pin "2") (pinfunction "2_2") (pintype "passive"))
      (node (ref "D1") (pin "1") (pinfunction "Cathode_1") (pintype "passive"))
      (node (ref "R236") (pin "1") (pinfunction "1_1") (pintype "passive"))
      (node (ref "U1") (pin "3") (pinfunction "VIN_3") (pintype "power_in"))
    )
    (net (code "85") (name "V_FET_P") (class "Default")
      (node (ref "C4") (pin "1") (pinfunction "1_1") (pintype "passive"))
      (node (ref "C5") (pin "1") (pinfunction "1_1") (pintype "passive"))
      (node (ref "C6") (pin "1") (pinfunction "1_1") (pintype "passive"))
      (node (ref "C7") (pin "1") (pinfunction "1_1") (pintype "passive"))
      (node (ref "J12") (pin "1") (pinfunction "1_1") (pintype "passive"))
      (node (ref "J12") (pin "3") (pinfunction "3_3") (pintype "passive"))
      (node (ref "J13") (pin "1") (pinfunction "1_1") (pintype "passive"))
      (node (ref "J13") (pin "3") (pinfunction "3_3") (pintype "passive"))
      (node (ref "J14") (pin "1") (pinfunction "1_1") (pintype "passive"))
      (node (ref "J14") (pin "3") (pinfunction "3_3") (pintype "passive"))
      (node (ref "J15") (pin "1") (pinfunction "1_1") (pintype "passive"))
      (node (ref "J15") (pin "3") (pinfunction "3_3") (pintype "passive"))
      (node (ref "J16") (pin "1") (pinfunction "1_1") (pintype "passive"))
      (node (ref "J16") (pin "3") (pinfunction "3_3") (pintype "passive"))
      (node (ref "J17") (pin "1") (pinfunction "1_1") (pintype "passive"))
      (node (ref "J17") (pin "3") (pinfunction "3_3") (pintype "passive"))
      (node (ref "J18") (pin "1") (pinfunction "1_1") (pintype "passive"))
      (node (ref "J18") (pin "3") (pinfunction "3_3") (pintype "passive"))
      (node (ref "J19") (pin "1") (pinfunction "1_1") (pintype "passive"))
      (node (ref "J19") (pin "3") (pinfunction "3_3") (pintype "passive"))
      (node (ref "Q1") (pin "1") (pinfunction "S_1") (pintype "passive"))
      (node (ref "U2") (pin "4") (pinfunction "CATHODE_4") (pintype "passive"))
    )
  )
)
